# sb-sonata-led.net
KiCad netlist of a schematic drawn in Altium Designer
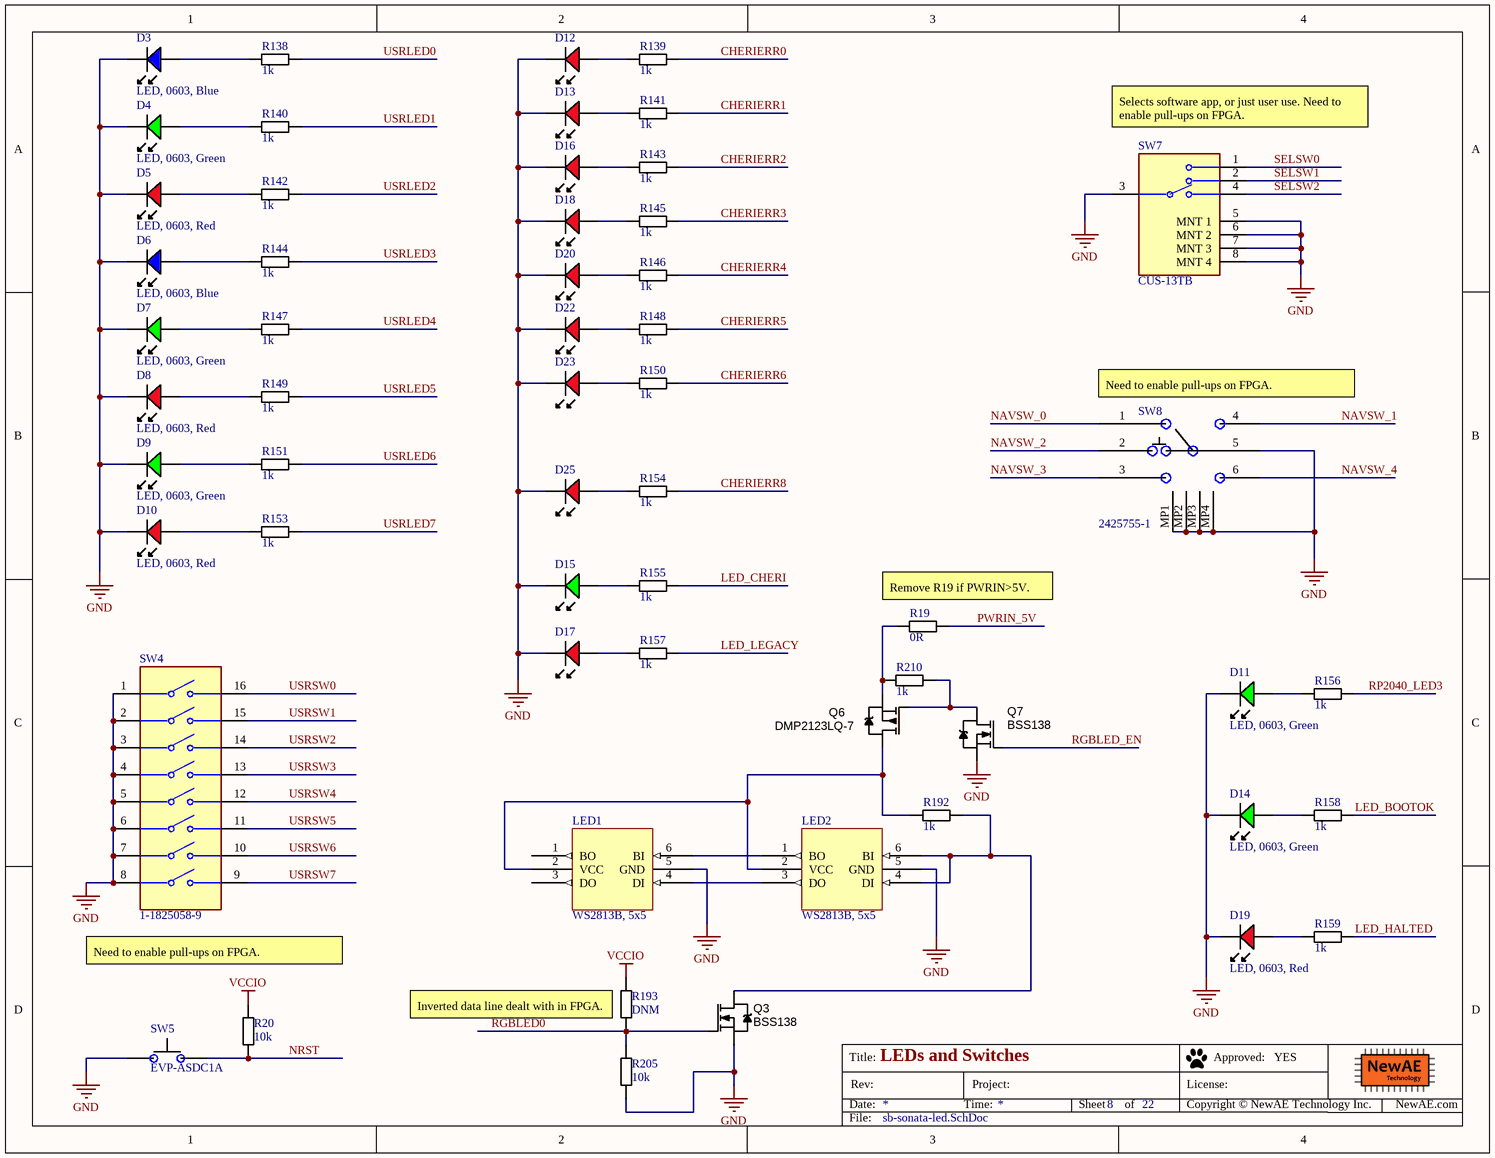
[diagram p0: sb-sonata-led.SchDoc]

(export (version "E")
  (design (tool "Eeschema 10.0.6"))
  (components
    (comp (ref "D3")
      (value "LED, 0603, Blue")
      (footprint "LED-0603-BLUE")
      (description "Chip LED, Blue")
      (fields (field (name "PART NUMBER") "LEDCHIP_0603_BLUE"))
      (libsource (lib "NewAE_AltiumLib") (part "LED_BLUE"))
    )
    (comp (ref "D4")
      (value "LED, 0603, Green")
      (footprint "LED-0603-GREEN")
      (description "Chip LED, Green")
      (fields (field (name "PART NUMBER") "LEDCHIP_0603_GREEN"))
      (libsource (lib "NewAE_AltiumLib") (part "LED_GREEN"))
    )
    (comp (ref "D5")
      (value "LED, 0603, Red")
      (footprint "LED-0603-RED")
      (description "Chip LED, Red")
      (fields (field (name "PART NUMBER") "LEDCHIP_0603_RED"))
      (libsource (lib "NewAE_AltiumLib") (part "LED_RED"))
    )
    (comp (ref "D6")
      (value "LED, 0603, Blue")
      (footprint "LED-0603-BLUE")
      (description "Chip LED, Blue")
      (fields (field (name "PART NUMBER") "LEDCHIP_0603_BLUE"))
      (libsource (lib "NewAE_AltiumLib") (part "LED_BLUE"))
    )
    (comp (ref "D7")
      (value "LED, 0603, Green")
      (footprint "LED-0603-GREEN")
      (description "Chip LED, Green")
      (fields (field (name "PART NUMBER") "LEDCHIP_0603_GREEN"))
      (libsource (lib "NewAE_AltiumLib") (part "LED_GREEN"))
    )
    (comp (ref "D8")
      (value "LED, 0603, Red")
      (footprint "LED-0603-RED")
      (description "Chip LED, Red")
      (fields (field (name "PART NUMBER") "LEDCHIP_0603_RED"))
      (libsource (lib "NewAE_AltiumLib") (part "LED_RED"))
    )
    (comp (ref "D9")
      (value "LED, 0603, Green")
      (footprint "LED-0603-GREEN")
      (description "Chip LED, Green")
      (fields (field (name "PART NUMBER") "LEDCHIP_0603_GREEN"))
      (libsource (lib "NewAE_AltiumLib") (part "LED_GREEN"))
    )
    (comp (ref "D10")
      (value "LED, 0603, Red")
      (footprint "LED-0603-RED")
      (description "Chip LED, Red")
      (fields (field (name "PART NUMBER") "LEDCHIP_0603_RED"))
      (libsource (lib "NewAE_AltiumLib") (part "LED_RED"))
    )
    (comp (ref "D11")
      (value "LED, 0603, Green")
      (footprint "LED-0603-GREEN")
      (description "Chip LED, Green")
      (fields (field (name "PART NUMBER") "LEDCHIP_0603_GREEN"))
      (libsource (lib "NewAE_AltiumLib") (part "LED_GREEN"))
    )
    (comp (ref "D12")
      (value "LED, 0603, Red")
      (footprint "LED-0603-RED")
      (description "Chip LED, Red")
      (fields (field (name "PART NUMBER") "LEDCHIP_0603_RED"))
      (libsource (lib "NewAE_AltiumLib") (part "LED_RED"))
    )
    (comp (ref "D13")
      (value "LED, 0603, Red")
      (footprint "LED-0603-RED")
      (description "Chip LED, Red")
      (fields (field (name "PART NUMBER") "LEDCHIP_0603_RED"))
      (libsource (lib "NewAE_AltiumLib") (part "LED_RED"))
    )
    (comp (ref "D14")
      (value "LED, 0603, Green")
      (footprint "LED-0603-GREEN")
      (description "Chip LED, Green")
      (fields (field (name "PART NUMBER") "LEDCHIP_0603_GREEN"))
      (libsource (lib "NewAE_AltiumLib") (part "LED_GREEN"))
    )
    (comp (ref "D15")
      (value "LED, 0603, Green")
      (footprint "LED-0603-GREEN")
      (description "Chip LED, Green")
      (fields (field (name "PART NUMBER") "LEDCHIP_0603_GREEN"))
      (libsource (lib "NewAE_AltiumLib") (part "LED_GREEN"))
    )
    (comp (ref "D16")
      (value "LED, 0603, Red")
      (footprint "LED-0603-RED")
      (description "Chip LED, Red")
      (fields (field (name "PART NUMBER") "LEDCHIP_0603_RED"))
      (libsource (lib "NewAE_AltiumLib") (part "LED_RED"))
    )
    (comp (ref "D17")
      (value "LED, 0603, Red")
      (footprint "LED-0603-RED")
      (description "Chip LED, Red")
      (fields (field (name "PART NUMBER") "LEDCHIP_0603_RED"))
      (libsource (lib "NewAE_AltiumLib") (part "LED_RED"))
    )
    (comp (ref "D18")
      (value "LED, 0603, Red")
      (footprint "LED-0603-RED")
      (description "Chip LED, Red")
      (fields (field (name "PART NUMBER") "LEDCHIP_0603_RED"))
      (libsource (lib "NewAE_AltiumLib") (part "LED_RED"))
    )
    (comp (ref "D19")
      (value "LED, 0603, Red")
      (footprint "LED-0603-RED")
      (description "Chip LED, Red")
      (fields (field (name "PART NUMBER") "LEDCHIP_0603_RED"))
      (libsource (lib "NewAE_AltiumLib") (part "LED_RED"))
    )
    (comp (ref "D20")
      (value "LED, 0603, Red")
      (footprint "LED-0603-RED")
      (description "Chip LED, Red")
      (fields (field (name "PART NUMBER") "LEDCHIP_0603_RED"))
      (libsource (lib "NewAE_AltiumLib") (part "LED_RED"))
    )
    (comp (ref "D22")
      (value "LED, 0603, Red")
      (footprint "LED-0603-RED")
      (description "Chip LED, Red")
      (fields (field (name "PART NUMBER") "LEDCHIP_0603_RED"))
      (libsource (lib "NewAE_AltiumLib") (part "LED_RED"))
    )
    (comp (ref "D23")
      (value "LED, 0603, Red")
      (footprint "LED-0603-RED")
      (description "Chip LED, Red")
      (fields (field (name "PART NUMBER") "LEDCHIP_0603_RED"))
      (libsource (lib "NewAE_AltiumLib") (part "LED_RED"))
    )
    (comp (ref "D25")
      (value "LED, 0603, Red")
      (footprint "LED-0603-RED")
      (description "Chip LED, Red")
      (fields (field (name "PART NUMBER") "LEDCHIP_0603_RED"))
      (libsource (lib "NewAE_AltiumLib") (part "LED_RED"))
    )
    (comp (ref "LED1")
      (value "WS2813B, 5x5")
      (footprint "WS2813B_5x5")
      (description "WS2813B, 5x5 SMD Neopixel")
      (fields (field (name "PART NUMBER") "WS2813B_5x5"))
      (libsource (lib "NewAE_AltiumLib") (part "WS2813B"))
    )
    (comp (ref "LED2")
      (value "WS2813B, 5x5")
      (footprint "WS2813B_5x5")
      (description "WS2813B, 5x5 SMD Neopixel")
      (fields (field (name "PART NUMBER") "WS2813B_5x5"))
      (libsource (lib "NewAE_AltiumLib") (part "WS2813B"))
    )
    (comp (ref "Q3")
      (value "BSS138")
      (footprint "SOT95P245X110-3M")
      (description "MOSFET N-CH 30V 2.2A SOT23-3")
      (libsource (lib "NewAE_AltiumLib") (part "MOSFET_N_GSD"))
    )
    (comp (ref "Q6")
      (value "DMP2123LQ-7")
      (footprint "SOT95P245X110-3M")
      (description "P-Channel, 3A, Logic Level")
      (libsource (lib "NewAE_AltiumLib") (part "MOSFET_P_GSD"))
    )
    (comp (ref "Q7")
      (value "BSS138")
      (footprint "SOT95P245X110-3M")
      (description "MOSFET N-CH 30V 2.2A SOT23-3")
      (libsource (lib "NewAE_AltiumLib") (part "MOSFET_N_GSD"))
    )
    (comp (ref "R19")
      (value "0R")
      (footprint "RESC1608X55N")
      (description "0R, 0603, 1/10W")
      (fields (field (name "PART NUMBER") "RCHIP-0R-0603") (field (name "TOLERANCE") "1%"))
      (libsource (lib "") (part "RES-EU_2"))
    )
    (comp (ref "R20")
      (value "10k")
      (footprint "RESC1005X40N")
      (description "10k res, 0402, 1%, 1/16W")
      (fields (field (name "PART NUMBER") "RCHIP-10K-0402") (field (name "TOLERANCE") "1%"))
      (libsource (lib "") (part "RES-EU_1"))
    )
    (comp (ref "R138")
      (value "1k")
      (footprint "RESC1005X40N")
      (description "1k res, 0402, 1%, 1/16W")
      (fields (field (name "PART NUMBER") "RCHIP-1K-0402") (field (name "TOLERANCE") "1%"))
      (libsource (lib "NewAE_AltiumLib") (part "RES-EU"))
    )
    (comp (ref "R139")
      (value "1k")
      (footprint "RESC1005X40N")
      (description "1k res, 0402, 1%, 1/16W")
      (fields (field (name "PART NUMBER") "RCHIP-1K-0402") (field (name "TOLERANCE") "1%"))
      (libsource (lib "NewAE_AltiumLib") (part "RES-EU"))
    )
    (comp (ref "R140")
      (value "1k")
      (footprint "RESC1005X40N")
      (description "1k res, 0402, 1%, 1/16W")
      (fields (field (name "PART NUMBER") "RCHIP-1K-0402") (field (name "TOLERANCE") "1%"))
      (libsource (lib "NewAE_AltiumLib") (part "RES-EU"))
    )
    (comp (ref "R141")
      (value "1k")
      (footprint "RESC1005X40N")
      (description "1k res, 0402, 1%, 1/16W")
      (fields (field (name "PART NUMBER") "RCHIP-1K-0402") (field (name "TOLERANCE") "1%"))
      (libsource (lib "NewAE_AltiumLib") (part "RES-EU"))
    )
    (comp (ref "R142")
      (value "1k")
      (footprint "RESC1005X40N")
      (description "1k res, 0402, 1%, 1/16W")
      (fields (field (name "PART NUMBER") "RCHIP-1K-0402") (field (name "TOLERANCE") "1%"))
      (libsource (lib "NewAE_AltiumLib") (part "RES-EU"))
    )
    (comp (ref "R143")
      (value "1k")
      (footprint "RESC1005X40N")
      (description "1k res, 0402, 1%, 1/16W")
      (fields (field (name "PART NUMBER") "RCHIP-1K-0402") (field (name "TOLERANCE") "1%"))
      (libsource (lib "NewAE_AltiumLib") (part "RES-EU"))
    )
    (comp (ref "R144")
      (value "1k")
      (footprint "RESC1005X40N")
      (description "1k res, 0402, 1%, 1/16W")
      (fields (field (name "PART NUMBER") "RCHIP-1K-0402") (field (name "TOLERANCE") "1%"))
      (libsource (lib "NewAE_AltiumLib") (part "RES-EU"))
    )
    (comp (ref "R145")
      (value "1k")
      (footprint "RESC1005X40N")
      (description "1k res, 0402, 1%, 1/16W")
      (fields (field (name "PART NUMBER") "RCHIP-1K-0402") (field (name "TOLERANCE") "1%"))
      (libsource (lib "NewAE_AltiumLib") (part "RES-EU"))
    )
    (comp (ref "R146")
      (value "1k")
      (footprint "RESC1005X40N")
      (description "1k res, 0402, 1%, 1/16W")
      (fields (field (name "PART NUMBER") "RCHIP-1K-0402") (field (name "TOLERANCE") "1%"))
      (libsource (lib "NewAE_AltiumLib") (part "RES-EU"))
    )
    (comp (ref "R147")
      (value "1k")
      (footprint "RESC1005X40N")
      (description "1k res, 0402, 1%, 1/16W")
      (fields (field (name "PART NUMBER") "RCHIP-1K-0402") (field (name "TOLERANCE") "1%"))
      (libsource (lib "NewAE_AltiumLib") (part "RES-EU"))
    )
    (comp (ref "R148")
      (value "1k")
      (footprint "RESC1005X40N")
      (description "1k res, 0402, 1%, 1/16W")
      (fields (field (name "PART NUMBER") "RCHIP-1K-0402") (field (name "TOLERANCE") "1%"))
      (libsource (lib "NewAE_AltiumLib") (part "RES-EU"))
    )
    (comp (ref "R149")
      (value "1k")
      (footprint "RESC1005X40N")
      (description "1k res, 0402, 1%, 1/16W")
      (fields (field (name "PART NUMBER") "RCHIP-1K-0402") (field (name "TOLERANCE") "1%"))
      (libsource (lib "NewAE_AltiumLib") (part "RES-EU"))
    )
    (comp (ref "R150")
      (value "1k")
      (footprint "RESC1005X40N")
      (description "1k res, 0402, 1%, 1/16W")
      (fields (field (name "PART NUMBER") "RCHIP-1K-0402") (field (name "TOLERANCE") "1%"))
      (libsource (lib "NewAE_AltiumLib") (part "RES-EU"))
    )
    (comp (ref "R151")
      (value "1k")
      (footprint "RESC1005X40N")
      (description "1k res, 0402, 1%, 1/16W")
      (fields (field (name "PART NUMBER") "RCHIP-1K-0402") (field (name "TOLERANCE") "1%"))
      (libsource (lib "NewAE_AltiumLib") (part "RES-EU"))
    )
    (comp (ref "R153")
      (value "1k")
      (footprint "RESC1005X40N")
      (description "1k res, 0402, 1%, 1/16W")
      (fields (field (name "PART NUMBER") "RCHIP-1K-0402") (field (name "TOLERANCE") "1%"))
      (libsource (lib "NewAE_AltiumLib") (part "RES-EU"))
    )
    (comp (ref "R154")
      (value "1k")
      (footprint "RESC1005X40N")
      (description "1k res, 0402, 1%, 1/16W")
      (fields (field (name "PART NUMBER") "RCHIP-1K-0402") (field (name "TOLERANCE") "1%"))
      (libsource (lib "NewAE_AltiumLib") (part "RES-EU"))
    )
    (comp (ref "R155")
      (value "1k")
      (footprint "RESC1005X40N")
      (description "1k res, 0402, 1%, 1/16W")
      (fields (field (name "PART NUMBER") "RCHIP-1K-0402") (field (name "TOLERANCE") "1%"))
      (libsource (lib "NewAE_AltiumLib") (part "RES-EU"))
    )
    (comp (ref "R156")
      (value "1k")
      (footprint "RESC1005X40N")
      (description "1k res, 0402, 1%, 1/16W")
      (fields (field (name "PART NUMBER") "RCHIP-1K-0402") (field (name "TOLERANCE") "1%"))
      (libsource (lib "NewAE_AltiumLib") (part "RES-EU"))
    )
    (comp (ref "R157")
      (value "1k")
      (footprint "RESC1005X40N")
      (description "1k res, 0402, 1%, 1/16W")
      (fields (field (name "PART NUMBER") "RCHIP-1K-0402") (field (name "TOLERANCE") "1%"))
      (libsource (lib "NewAE_AltiumLib") (part "RES-EU"))
    )
    (comp (ref "R158")
      (value "1k")
      (footprint "RESC1005X40N")
      (description "1k res, 0402, 1%, 1/16W")
      (fields (field (name "PART NUMBER") "RCHIP-1K-0402") (field (name "TOLERANCE") "1%"))
      (libsource (lib "NewAE_AltiumLib") (part "RES-EU"))
    )
    (comp (ref "R159")
      (value "1k")
      (footprint "RESC1005X40N")
      (description "1k res, 0402, 1%, 1/16W")
      (fields (field (name "PART NUMBER") "RCHIP-1K-0402") (field (name "TOLERANCE") "1%"))
      (libsource (lib "NewAE_AltiumLib") (part "RES-EU"))
    )
    (comp (ref "R192")
      (value "1k")
      (footprint "RESC1005X40N")
      (description "1k res, 0402, 1%, 1/16W")
      (fields (field (name "PART NUMBER") "RCHIP-1K-0402") (field (name "TOLERANCE") "1%"))
      (libsource (lib "") (part "RES-EU_2"))
    )
    (comp (ref "R193")
      (value "DNM")
      (footprint "RESC1005X40N")
      (fields (field (name "PART NUMBER") "RCHIP-DNM-0402"))
      (libsource (lib "") (part "RES-EU_1"))
    )
    (comp (ref "R205")
      (value "10k")
      (footprint "RESC1005X40N")
      (description "10k res, 0402, 1%, 1/16W")
      (fields (field (name "PART NUMBER") "RCHIP-10K-0402") (field (name "TOLERANCE") "1%"))
      (libsource (lib "") (part "RES-EU_1"))
    )
    (comp (ref "R210")
      (value "1k")
      (footprint "RESC1005X40N")
      (description "1k res, 0402, 1%, 1/16W")
      (fields (field (name "PART NUMBER") "RCHIP-1K-0402") (field (name "TOLERANCE") "1%"))
      (libsource (lib "NewAE_AltiumLib") (part "RES-EU"))
    )
    (comp (ref "SW4")
      (value "1-1825058-9")
      (footprint "FP-1-1825058-9-MFG")
      (description "SWITCH SLIDE DIP SPST 100MA 24V")
      (fields
        (field (name "MANUFACTURER") "TE Connectivity")
        (field (name "OCTOPART") "https://octopart.com/1-1825058-9-te+connectivity-46507285")
      )
      (libsource (lib "Altium Content Vault") (part "88b473189f0daa5e8e83a09a3141fee"))
    )
    (comp (ref "SW5")
      (value "EVP-ASDC1A")
      (footprint "EVPAS")
      (description "Pushbutton, SMD, 2.5NM force, NO")
      (libsource (lib "NewAE_AltiumLib") (part "SW_PB_NO_2PIN"))
    )
    (comp (ref "SW7")
      (value "CUS-13TB")
      (footprint "FP-CUS-13TB-MFG")
      (description "SWITCH SLIDE SP3T 300MA 4V")
      (libsource (lib "Altium Content Vault") (part "47bcb96ef67674530f45e4053201745"))
    )
    (comp (ref "SW8")
      (value "2425755-1")
      (footprint "2425755-1")
      (description "5-Way Joystick")
      (libsource (lib "NewAE_AltiumLib") (part "SW_5WAY_4MP"))
    )
  )
  (nets
    (net (code "1") (name "/CHERIERR0") (class "Default")
      (node (ref "R139") (pin "1") (pinfunction "1_1") (pintype "passive"))
    )
    (net (code "2") (name "/CHERIERR1") (class "Default")
      (node (ref "R141") (pin "1") (pinfunction "1_1") (pintype "passive"))
    )
    (net (code "3") (name "/CHERIERR2") (class "Default")
      (node (ref "R143") (pin "1") (pinfunction "1_1") (pintype "passive"))
    )
    (net (code "4") (name "/CHERIERR3") (class "Default")
      (node (ref "R145") (pin "1") (pinfunction "1_1") (pintype "passive"))
    )
    (net (code "5") (name "/CHERIERR4") (class "Default")
      (node (ref "R146") (pin "1") (pinfunction "1_1") (pintype "passive"))
    )
    (net (code "6") (name "/CHERIERR5") (class "Default")
      (node (ref "R148") (pin "1") (pinfunction "1_1") (pintype "passive"))
    )
    (net (code "7") (name "/CHERIERR6") (class "Default")
      (node (ref "R150") (pin "1") (pinfunction "1_1") (pintype "passive"))
    )
    (net (code "8") (name "/CHERIERR8") (class "Default")
      (node (ref "R154") (pin "1") (pinfunction "1_1") (pintype "passive"))
    )
    (net (code "9") (name "/LED_BOOTOK") (class "Default")
      (node (ref "R158") (pin "1") (pinfunction "1_1") (pintype "passive"))
    )
    (net (code "10") (name "/LED_CHERI") (class "Default")
      (node (ref "R155") (pin "1") (pinfunction "1_1") (pintype "passive"))
    )
    (net (code "11") (name "/LED_HALTED") (class "Default")
      (node (ref "R159") (pin "1") (pinfunction "1_1") (pintype "passive"))
    )
    (net (code "12") (name "/LED_LEGACY") (class "Default")
      (node (ref "R157") (pin "1") (pinfunction "1_1") (pintype "passive"))
    )
    (net (code "13") (name "/NAVSW_0") (class "Default")
      (node (ref "SW8") (pin "1") (pinfunction "1_1") (pintype "passive"))
    )
    (net (code "14") (name "/NAVSW_1") (class "Default")
      (node (ref "SW8") (pin "4") (pinfunction "4_4") (pintype "passive"))
    )
    (net (code "15") (name "/NAVSW_2") (class "Default")
      (node (ref "SW8") (pin "2") (pinfunction "2_2") (pintype "passive"))
    )
    (net (code "16") (name "/NAVSW_3") (class "Default")
      (node (ref "SW8") (pin "3") (pinfunction "3_3") (pintype "passive"))
    )
    (net (code "17") (name "/NAVSW_4") (class "Default")
      (node (ref "SW8") (pin "6") (pinfunction "6_6") (pintype "passive"))
    )
    (net (code "18") (name "/NRST") (class "Default")
      (node (ref "R20") (pin "2") (pinfunction "2_2") (pintype "passive"))
      (node (ref "SW5") (pin "2") (pinfunction "IN_2") (pintype "passive"))
    )
    (net (code "19") (name "/PWRIN_5V") (class "Default")
      (node (ref "R19") (pin "2") (pinfunction "2_2") (pintype "passive"))
    )
    (net (code "20") (name "/RGBLED0") (class "Default")
      (node (ref "Q3") (pin "1") (pinfunction "G_1") (pintype "passive"))
      (node (ref "R193") (pin "2") (pinfunction "2_2") (pintype "passive"))
      (node (ref "R205") (pin "1") (pinfunction "1_1") (pintype "passive"))
    )
    (net (code "21") (name "/RGBLED_EN") (class "Default")
      (node (ref "Q7") (pin "1") (pinfunction "G_1") (pintype "passive"))
    )
    (net (code "22") (name "/RP2040_LED3") (class "Default")
      (node (ref "R156") (pin "1") (pinfunction "1_1") (pintype "passive"))
    )
    (net (code "23") (name "/SELSW0") (class "Default")
      (node (ref "SW7") (pin "1") (pinfunction "1_1") (pintype "passive"))
    )
    (net (code "24") (name "/SELSW1") (class "Default")
      (node (ref "SW7") (pin "2") (pinfunction "2_2") (pintype "passive"))
    )
    (net (code "25") (name "/SELSW2") (class "Default")
      (node (ref "SW7") (pin "4") (pinfunction "4_4") (pintype "passive"))
    )
    (net (code "26") (name "/USRLED0") (class "Default")
      (node (ref "R138") (pin "1") (pinfunction "1_1") (pintype "passive"))
    )
    (net (code "27") (name "/USRLED1") (class "Default")
      (node (ref "R140") (pin "1") (pinfunction "1_1") (pintype "passive"))
    )
    (net (code "28") (name "/USRLED2") (class "Default")
      (node (ref "R142") (pin "1") (pinfunction "1_1") (pintype "passive"))
    )
    (net (code "29") (name "/USRLED3") (class "Default")
      (node (ref "R144") (pin "1") (pinfunction "1_1") (pintype "passive"))
    )
    (net (code "30") (name "/USRLED4") (class "Default")
      (node (ref "R147") (pin "1") (pinfunction "1_1") (pintype "passive"))
    )
    (net (code "31") (name "/USRLED5") (class "Default")
      (node (ref "R149") (pin "1") (pinfunction "1_1") (pintype "passive"))
    )
    (net (code "32") (name "/USRLED6") (class "Default")
      (node (ref "R151") (pin "1") (pinfunction "1_1") (pintype "passive"))
    )
    (net (code "33") (name "/USRLED7") (class "Default")
      (node (ref "R153") (pin "1") (pinfunction "1_1") (pintype "passive"))
    )
    (net (code "34") (name "/USRSW0") (class "Default")
      (node (ref "SW4") (pin "16") (pinfunction "16_16") (pintype "passive"))
    )
    (net (code "35") (name "/USRSW1") (class "Default")
      (node (ref "SW4") (pin "15") (pinfunction "15_15") (pintype "passive"))
    )
    (net (code "36") (name "/USRSW2") (class "Default")
      (node (ref "SW4") (pin "14") (pinfunction "14_14") (pintype "passive"))
    )
    (net (code "37") (name "/USRSW3") (class "Default")
      (node (ref "SW4") (pin "13") (pinfunction "13_13") (pintype "passive"))
    )
    (net (code "38") (name "/USRSW4") (class "Default")
      (node (ref "SW4") (pin "12") (pinfunction "12_12") (pintype "passive"))
    )
    (net (code "39") (name "/USRSW5") (class "Default")
      (node (ref "SW4") (pin "11") (pinfunction "11_11") (pintype "passive"))
    )
    (net (code "40") (name "/USRSW6") (class "Default")
      (node (ref "SW4") (pin "10") (pinfunction "10_10") (pintype "passive"))
    )
    (net (code "41") (name "/USRSW7") (class "Default")
      (node (ref "SW4") (pin "9") (pinfunction "9_9") (pintype "passive"))
    )
    (net (code "42") (name "GND") (class "Default")
      (node (ref "D10") (pin "K") (pinfunction "K_K") (pintype "passive"))
      (node (ref "D11") (pin "K") (pinfunction "K_K") (pintype "passive"))
      (node (ref "D12") (pin "K") (pinfunction "K_K") (pintype "passive"))
      (node (ref "D13") (pin "K") (pinfunction "K_K") (pintype "passive"))
      (node (ref "D14") (pin "K") (pinfunction "K_K") (pintype "passive"))
      (node (ref "D15") (pin "K") (pinfunction "K_K") (pintype "passive"))
      (node (ref "D16") (pin "K") (pinfunction "K_K") (pintype "passive"))
      (node (ref "D17") (pin "K") (pinfunction "K_K") (pintype "passive"))
      (node (ref "D18") (pin "K") (pinfunction "K_K") (pintype "passive"))
      (node (ref "D19") (pin "K") (pinfunction "K_K") (pintype "passive"))
      (node (ref "D20") (pin "K") (pinfunction "K_K") (pintype "passive"))
      (node (ref "D22") (pin "K") (pinfunction "K_K") (pintype "passive"))
      (node (ref "D23") (pin "K") (pinfunction "K_K") (pintype "passive"))
      (node (ref "D25") (pin "K") (pinfunction "K_K") (pintype "passive"))
      (node (ref "D3") (pin "K") (pinfunction "K_K") (pintype "passive"))
      (node (ref "D4") (pin "K") (pinfunction "K_K") (pintype "passive"))
      (node (ref "D5") (pin "K") (pinfunction "K_K") (pintype "passive"))
      (node (ref "D6") (pin "K") (pinfunction "K_K") (pintype "passive"))
      (node (ref "D7") (pin "K") (pinfunction "K_K") (pintype "passive"))
      (node (ref "D8") (pin "K") (pinfunction "K_K") (pintype "passive"))
      (node (ref "D9") (pin "K") (pinfunction "K_K") (pintype "passive"))
      (node (ref "LED1") (pin "5") (pinfunction "GND_5") (pintype "passive"))
      (node (ref "LED2") (pin "5") (pinfunction "GND_5") (pintype "passive"))
      (node (ref "Q3") (pin "2") (pinfunction "S_2") (pintype "passive"))
      (node (ref "Q7") (pin "2") (pinfunction "S_2") (pintype "passive"))
      (node (ref "R205") (pin "2") (pinfunction "2_2") (pintype "passive"))
      (node (ref "SW4") (pin "1") (pinfunction "1_1") (pintype "passive"))
      (node (ref "SW4") (pin "2") (pinfunction "2_2") (pintype "passive"))
      (node (ref "SW4") (pin "3") (pinfunction "3_3") (pintype "passive"))
      (node (ref "SW4") (pin "4") (pinfunction "4_4") (pintype "passive"))
      (node (ref "SW4") (pin "5") (pinfunction "5_5") (pintype "passive"))
      (node (ref "SW4") (pin "6") (pinfunction "6_6") (pintype "passive"))
      (node (ref "SW4") (pin "7") (pinfunction "7_7") (pintype "passive"))
      (node (ref "SW4") (pin "8") (pinfunction "8_8") (pintype "passive"))
      (node (ref "SW5") (pin "1") (pinfunction "IN_1") (pintype "passive"))
      (node (ref "SW7") (pin "3") (pinfunction "C_3") (pintype "passive"))
      (node (ref "SW7") (pin "5") (pinfunction "MNT_1_5") (pintype "passive"))
      (node (ref "SW7") (pin "6") (pinfunction "MNT_2_6") (pintype "passive"))
      (node (ref "SW7") (pin "7") (pinfunction "MNT_3_7") (pintype "passive"))
      (node (ref "SW7") (pin "8") (pinfunction "MNT_4_8") (pintype "passive"))
      (node (ref "SW8") (pin "5") (pinfunction "5_5") (pintype "passive"))
      (node (ref "SW8") (pin "MP1") (pinfunction "MP1_MP1") (pintype "passive"))
      (node (ref "SW8") (pin "MP2") (pinfunction "MP2_MP2") (pintype "passive"))
      (node (ref "SW8") (pin "MP3") (pinfunction "MP3_MP3") (pintype "passive"))
      (node (ref "SW8") (pin "MP4") (pinfunction "MP4_MP4") (pintype "passive"))
    )
    (net (code "43") (name "Net-(D3-PadA)") (class "Default")
      (node (ref "D3") (pin "A") (pinfunction "A_A") (pintype "passive"))
      (node (ref "R138") (pin "2") (pinfunction "2_2") (pintype "passive"))
    )
    (net (code "44") (name "Net-(D4-PadA)") (class "Default")
      (node (ref "D4") (pin "A") (pinfunction "A_A") (pintype "passive"))
      (node (ref "R140") (pin "2") (pinfunction "2_2") (pintype "passive"))
    )
    (net (code "45") (name "Net-(D5-PadA)") (class "Default")
      (node (ref "D5") (pin "A") (pinfunction "A_A") (pintype "passive"))
      (node (ref "R142") (pin "2") (pinfunction "2_2") (pintype "passive"))
    )
    (net (code "46") (name "Net-(D6-PadA)") (class "Default")
      (node (ref "D6") (pin "A") (pinfunction "A_A") (pintype "passive"))
      (node (ref "R144") (pin "2") (pinfunction "2_2") (pintype "passive"))
    )
    (net (code "47") (name "Net-(D7-PadA)") (class "Default")
      (node (ref "D7") (pin "A") (pinfunction "A_A") (pintype "passive"))
      (node (ref "R147") (pin "2") (pinfunction "2_2") (pintype "passive"))
    )
    (net (code "48") (name "Net-(D8-PadA)") (class "Default")
      (node (ref "D8") (pin "A") (pinfunction "A_A") (pintype "passive"))
      (node (ref "R149") (pin "2") (pinfunction "2_2") (pintype "passive"))
    )
    (net (code "49") (name "Net-(D9-PadA)") (class "Default")
      (node (ref "D9") (pin "A") (pinfunction "A_A") (pintype "passive"))
      (node (ref "R151") (pin "2") (pinfunction "2_2") (pintype "passive"))
    )
    (net (code "50") (name "Net-(D10-PadA)") (class "Default")
      (node (ref "D10") (pin "A") (pinfunction "A_A") (pintype "passive"))
      (node (ref "R153") (pin "2") (pinfunction "2_2") (pintype "passive"))
    )
    (net (code "51") (name "Net-(D11-PadA)") (class "Default")
      (node (ref "D11") (pin "A") (pinfunction "A_A") (pintype "passive"))
      (node (ref "R156") (pin "2") (pinfunction "2_2") (pintype "passive"))
    )
    (net (code "52") (name "Net-(D12-PadA)") (class "Default")
      (node (ref "D12") (pin "A") (pinfunction "A_A") (pintype "passive"))
      (node (ref "R139") (pin "2") (pinfunction "2_2") (pintype "passive"))
    )
    (net (code "53") (name "Net-(D13-PadA)") (class "Default")
      (node (ref "D13") (pin "A") (pinfunction "A_A") (pintype "passive"))
      (node (ref "R141") (pin "2") (pinfunction "2_2") (pintype "passive"))
    )
    (net (code "54") (name "Net-(D14-PadA)") (class "Default")
      (node (ref "D14") (pin "A") (pinfunction "A_A") (pintype "passive"))
      (node (ref "R158") (pin "2") (pinfunction "2_2") (pintype "passive"))
    )
    (net (code "55") (name "Net-(D15-PadA)") (class "Default")
      (node (ref "D15") (pin "A") (pinfunction "A_A") (pintype "passive"))
      (node (ref "R155") (pin "2") (pinfunction "2_2") (pintype "passive"))
    )
    (net (code "56") (name "Net-(D16-PadA)") (class "Default")
      (node (ref "D16") (pin "A") (pinfunction "A_A") (pintype "passive"))
      (node (ref "R143") (pin "2") (pinfunction "2_2") (pintype "passive"))
    )
    (net (code "57") (name "Net-(D17-PadA)") (class "Default")
      (node (ref "D17") (pin "A") (pinfunction "A_A") (pintype "passive"))
      (node (ref "R157") (pin "2") (pinfunction "2_2") (pintype "passive"))
    )
    (net (code "58") (name "Net-(D18-PadA)") (class "Default")
      (node (ref "D18") (pin "A") (pinfunction "A_A") (pintype "passive"))
      (node (ref "R145") (pin "2") (pinfunction "2_2") (pintype "passive"))
    )
    (net (code "59") (name "Net-(D19-PadA)") (class "Default")
      (node (ref "D19") (pin "A") (pinfunction "A_A") (pintype "passive"))
      (node (ref "R159") (pin "2") (pinfunction "2_2") (pintype "passive"))
    )
    (net (code "60") (name "Net-(D20-PadA)") (class "Default")
      (node (ref "D20") (pin "A") (pinfunction "A_A") (pintype "passive"))
      (node (ref "R146") (pin "2") (pinfunction "2_2") (pintype "passive"))
    )
    (net (code "61") (name "Net-(D22-PadA)") (class "Default")
      (node (ref "D22") (pin "A") (pinfunction "A_A") (pintype "passive"))
      (node (ref "R148") (pin "2") (pinfunction "2_2") (pintype "passive"))
    )
    (net (code "62") (name "Net-(D23-PadA)") (class "Default")
      (node (ref "D23") (pin "A") (pinfunction "A_A") (pintype "passive"))
      (node (ref "R150") (pin "2") (pinfunction "2_2") (pintype "passive"))
    )
    (net (code "63") (name "Net-(D25-PadA)") (class "Default")
      (node (ref "D25") (pin "A") (pinfunction "A_A") (pintype "passive"))
      (node (ref "R154") (pin "2") (pinfunction "2_2") (pintype "passive"))
    )
    (net (code "64") (name "Net-(LED1-BI)") (class "Default")
      (node (ref "LED1") (pin "6") (pinfunction "BI_6") (pintype "input"))
      (node (ref "LED2") (pin "1") (pinfunction "BO_1") (pintype "output"))
    )
    (net (code "65") (name "Net-(LED1-DI)") (class "Default")
      (node (ref "LED1") (pin "4") (pinfunction "DI_4") (pintype "input"))
      (node (ref "LED2") (pin "3") (pinfunction "DO_3") (pintype "output"))
    )
    (net (code "66") (name "Net-(LED1-VCC)") (class "Default")
      (node (ref "LED1") (pin "2") (pinfunction "VCC_2") (pintype "passive"))
      (node (ref "LED2") (pin "2") (pinfunction "VCC_2") (pintype "passive"))
      (node (ref "Q6") (pin "3") (pinfunction "D_3") (pintype "passive"))
      (node (ref "R192") (pin "1") (pinfunction "1_1") (pintype "passive"))
    )
    (net (code "67") (name "Net-(LED2-BI)") (class "Default")
      (node (ref "LED2") (pin "4") (pinfunction "DI_4") (pintype "input"))
      (node (ref "LED2") (pin "6") (pinfunction "BI_6") (pintype "input"))
      (node (ref "Q3") (pin "3") (pinfunction "D_3") (pintype "passive"))
      (node (ref "R192") (pin "2") (pinfunction "2_2") (pintype "passive"))
    )
    (net (code "68") (name "Net-(Q6-G)") (class "Default")
      (node (ref "Q6") (pin "1") (pinfunction "G_1") (pintype "passive"))
      (node (ref "Q7") (pin "3") (pinfunction "D_3") (pintype "passive"))
      (node (ref "R210") (pin "1") (pinfunction "1_1") (pintype "passive"))
    )
    (net (code "69") (name "Net-(Q6-S)") (class "Default")
      (node (ref "Q6") (pin "2") (pinfunction "S_2") (pintype "passive"))
      (node (ref "R19") (pin "1") (pinfunction "1_1") (pintype "passive"))
      (node (ref "R210") (pin "2") (pinfunction "2_2") (pintype "passive"))
    )
    (net (code "70") (name "VCCIO") (class "Default")
      (node (ref "R193") (pin "1") (pinfunction "1_1") (pintype "passive"))
      (node (ref "R20") (pin "1") (pinfunction "1_1") (pintype "passive"))
    )
    (net (code "71") (name "unconnected-(LED1-BO-Pad1)") (class "Default")
      (node (ref "LED1") (pin "1") (pinfunction "BO_1") (pintype "output"))
    )
    (net (code "72") (name "unconnected-(LED1-DO-Pad3)") (class "Default")
      (node (ref "LED1") (pin "3") (pinfunction "DO_3") (pintype "output"))
    )
  )
)
